# databank.net
KiCad netlist of a schematic drawn in EAGLE
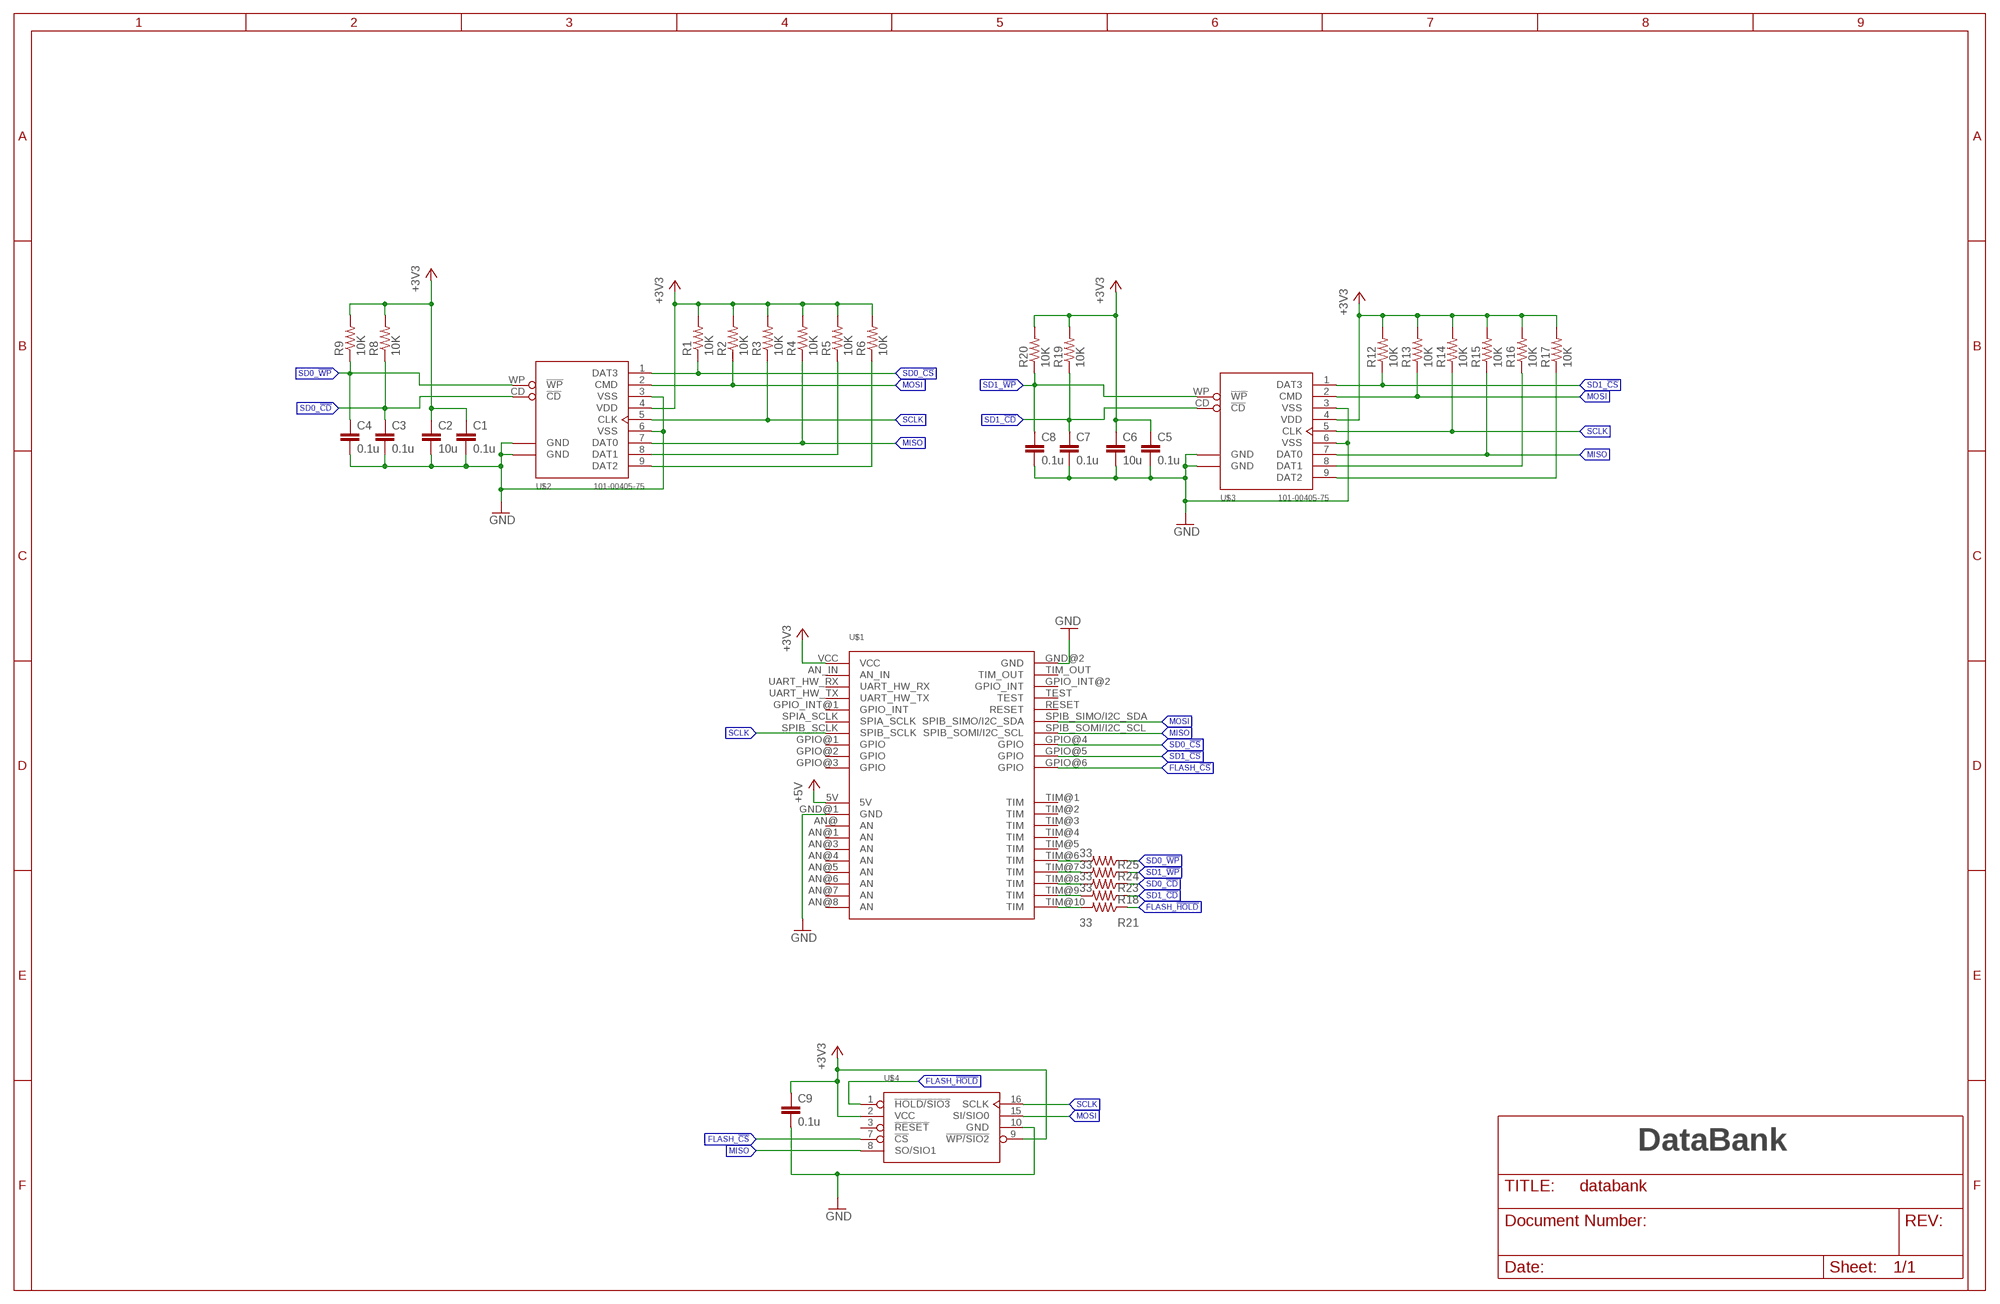
[diagram p0: schematic, sheet 1]

(export (version "E")
  (design (tool "Eeschema 10.0.6"))
  (components
    (comp (ref "C1")
      (value "0.1u")
      (footprint "eagle-import:C0603")
      (fields (field (name "MPN") "VJ0603V104ZXXCW1BC"))
      (libsource (lib "eagle-import") (part "C-EUC0603"))
    )
    (comp (ref "C2")
      (value "10u")
      (footprint "eagle-import:C0603")
      (fields (field (name "MPN") "LMK107BBJ106MALT"))
      (libsource (lib "eagle-import") (part "C-EUC0603"))
    )
    (comp (ref "C3")
      (value "0.1u")
      (footprint "eagle-import:C0603")
      (fields (field (name "MPN") "VJ0603V104ZXXCW1BC"))
      (libsource (lib "eagle-import") (part "C-EUC0603"))
    )
    (comp (ref "C4")
      (value "0.1u")
      (footprint "eagle-import:C0603")
      (fields (field (name "MPN") "VJ0603V104ZXXCW1BC"))
      (libsource (lib "eagle-import") (part "C-EUC0603"))
    )
    (comp (ref "C5")
      (value "0.1u")
      (footprint "eagle-import:C0603")
      (fields (field (name "MPN") "VJ0603V104ZXXCW1BC"))
      (libsource (lib "eagle-import") (part "C-EUC0603"))
    )
    (comp (ref "C6")
      (value "10u")
      (footprint "eagle-import:C0603")
      (fields (field (name "MPN") "LMK107BBJ106MALT"))
      (libsource (lib "eagle-import") (part "C-EUC0603"))
    )
    (comp (ref "C7")
      (value "0.1u")
      (footprint "eagle-import:C0603")
      (fields (field (name "MPN") "VJ0603V104ZXXCW1BC"))
      (libsource (lib "eagle-import") (part "C-EUC0603"))
    )
    (comp (ref "C8")
      (value "0.1u")
      (footprint "eagle-import:C0603")
      (fields (field (name "MPN") "VJ0603V104ZXXCW1BC"))
      (libsource (lib "eagle-import") (part "C-EUC0603"))
    )
    (comp (ref "C9")
      (value "0.1u")
      (footprint "eagle-import:C0603")
      (fields (field (name "MPN") "VJ0603V104ZXXCW1BC"))
      (libsource (lib "eagle-import") (part "C-EUC0603"))
    )
    (comp (ref "R1")
      (value "10K")
      (footprint "eagle-import:R0603")
      (fields (field (name "MPN") "WR06X1002FTL"))
      (libsource (lib "eagle-import") (part "R-US_R0603"))
    )
    (comp (ref "R2")
      (value "10K")
      (footprint "eagle-import:R0603")
      (fields (field (name "MPN") "WR06X1002FTL"))
      (libsource (lib "eagle-import") (part "R-US_R0603"))
    )
    (comp (ref "R3")
      (value "10K")
      (footprint "eagle-import:R0603")
      (fields (field (name "MPN") "WR06X1002FTL"))
      (libsource (lib "eagle-import") (part "R-US_R0603"))
    )
    (comp (ref "R4")
      (value "10K")
      (footprint "eagle-import:R0603")
      (fields (field (name "MPN") "WR06X1002FTL"))
      (libsource (lib "eagle-import") (part "R-US_R0603"))
    )
    (comp (ref "R5")
      (value "10K")
      (footprint "eagle-import:R0603")
      (fields (field (name "MPN") "WR06X1002FTL"))
      (libsource (lib "eagle-import") (part "R-US_R0603"))
    )
    (comp (ref "R6")
      (value "10K")
      (footprint "eagle-import:R0603")
      (fields (field (name "MPN") "WR06X1002FTL"))
      (libsource (lib "eagle-import") (part "R-US_R0603"))
    )
    (comp (ref "R8")
      (value "10K")
      (footprint "eagle-import:R0603")
      (fields (field (name "MPN") "WR06X1002FTL"))
      (libsource (lib "eagle-import") (part "R-US_R0603"))
    )
    (comp (ref "R9")
      (value "10K")
      (footprint "eagle-import:R0603")
      (fields (field (name "MPN") "WR06X1002FTL"))
      (libsource (lib "eagle-import") (part "R-US_R0603"))
    )
    (comp (ref "R12")
      (value "10K")
      (footprint "eagle-import:R0603")
      (fields (field (name "MPN") "WR06X1002FTL"))
      (libsource (lib "eagle-import") (part "R-US_R0603"))
    )
    (comp (ref "R13")
      (value "10K")
      (footprint "eagle-import:R0603")
      (fields (field (name "MPN") "WR06X1002FTL"))
      (libsource (lib "eagle-import") (part "R-US_R0603"))
    )
    (comp (ref "R14")
      (value "10K")
      (footprint "eagle-import:R0603")
      (fields (field (name "MPN") "WR06X1002FTL"))
      (libsource (lib "eagle-import") (part "R-US_R0603"))
    )
    (comp (ref "R15")
      (value "10K")
      (footprint "eagle-import:R0603")
      (fields (field (name "MPN") "WR06X1002FTL"))
      (libsource (lib "eagle-import") (part "R-US_R0603"))
    )
    (comp (ref "R16")
      (value "10K")
      (footprint "eagle-import:R0603")
      (fields (field (name "MPN") "WR06X1002FTL"))
      (libsource (lib "eagle-import") (part "R-US_R0603"))
    )
    (comp (ref "R17")
      (value "10K")
      (footprint "eagle-import:R0603")
      (fields (field (name "MPN") "WR06X1002FTL"))
      (libsource (lib "eagle-import") (part "R-US_R0603"))
    )
    (comp (ref "R18")
      (value "33")
      (footprint "eagle-import:R0603")
      (fields (field (name "MPN") "CR0402-JW-330GLF"))
      (libsource (lib "eagle-import") (part "R-US_R0603"))
    )
    (comp (ref "R19")
      (value "10K")
      (footprint "eagle-import:R0603")
      (fields (field (name "MPN") "WR06X1002FTL"))
      (libsource (lib "eagle-import") (part "R-US_R0603"))
    )
    (comp (ref "R20")
      (value "10K")
      (footprint "eagle-import:R0603")
      (fields (field (name "MPN") "WR06X1002FTL"))
      (libsource (lib "eagle-import") (part "R-US_R0603"))
    )
    (comp (ref "R21")
      (value "33")
      (footprint "eagle-import:R0603")
      (fields (field (name "MPN") "CR0402-JW-330GLF"))
      (libsource (lib "eagle-import") (part "R-US_R0603"))
    )
    (comp (ref "R23")
      (value "33")
      (footprint "eagle-import:R0603")
      (fields (field (name "MPN") "CR0402-JW-330GLF"))
      (libsource (lib "eagle-import") (part "R-US_R0603"))
    )
    (comp (ref "R24")
      (value "33")
      (footprint "eagle-import:R0603")
      (fields (field (name "MPN") "CR0402-JW-330GLF"))
      (libsource (lib "eagle-import") (part "R-US_R0603"))
    )
    (comp (ref "R25")
      (value "33")
      (footprint "eagle-import:R0603")
      (fields (field (name "MPN") "CR0402-JW-330GLF"))
      (libsource (lib "eagle-import") (part "R-US_R0603"))
    )
    (comp (ref "U$1")
      (value "LAUNCHPAD_BOOSTER_PACK")
      (footprint "eagle-import:LAUNCHPAD_BOOSTER_PACK")
      (libsource (lib "eagle-import") (part "LAUNCHPAD_BOOSTER_PACK"))
    )
    (comp (ref "U$2")
      (value "101-00405-75")
      (footprint "eagle-import:101-00405-75")
      (libsource (lib "eagle-import") (part "101-00405-75"))
    )
    (comp (ref "U$3")
      (value "101-00405-75")
      (footprint "eagle-import:101-00405-75")
      (libsource (lib "eagle-import") (part "101-00405-75"))
    )
    (comp (ref "U$4")
      (value "MX25L25635E")
      (footprint "eagle-import:SO-16LD")
      (libsource (lib "eagle-import") (part "MX25L25635E"))
    )
  )
  (nets
    (net (code "1") (name "+3V3") (class "Default")
      (node (ref "C1") (pin "1") (pinfunction "1_1") (pintype "passive"))
      (node (ref "C2") (pin "1") (pinfunction "1_1") (pintype "passive"))
      (node (ref "C5") (pin "1") (pinfunction "1_1") (pintype "passive"))
      (node (ref "C6") (pin "1") (pinfunction "1_1") (pintype "passive"))
      (node (ref "C9") (pin "1") (pinfunction "1_1") (pintype "passive"))
      (node (ref "R1") (pin "2") (pinfunction "2_2") (pintype "passive"))
      (node (ref "R12") (pin "2") (pinfunction "2_2") (pintype "passive"))
      (node (ref "R13") (pin "2") (pinfunction "2_2") (pintype "passive"))
      (node (ref "R14") (pin "2") (pinfunction "2_2") (pintype "passive"))
      (node (ref "R15") (pin "2") (pinfunction "2_2") (pintype "passive"))
      (node (ref "R16") (pin "2") (pinfunction "2_2") (pintype "passive"))
      (node (ref "R17") (pin "2") (pinfunction "2_2") (pintype "passive"))
      (node (ref "R19") (pin "2") (pinfunction "2_2") (pintype "passive"))
      (node (ref "R2") (pin "2") (pinfunction "2_2") (pintype "passive"))
      (node (ref "R20") (pin "2") (pinfunction "2_2") (pintype "passive"))
      (node (ref "R3") (pin "2") (pinfunction "2_2") (pintype "passive"))
      (node (ref "R4") (pin "2") (pinfunction "2_2") (pintype "passive"))
      (node (ref "R5") (pin "2") (pinfunction "2_2") (pintype "passive"))
      (node (ref "R6") (pin "2") (pinfunction "2_2") (pintype "passive"))
      (node (ref "R8") (pin "2") (pinfunction "2_2") (pintype "passive"))
      (node (ref "R9") (pin "2") (pinfunction "2_2") (pintype "passive"))
      (node (ref "U$1") (pin "VCC") (pinfunction "VCC_VCC") (pintype "power_in"))
      (node (ref "U$2") (pin "4") (pinfunction "VDD_4") (pintype "power_in"))
      (node (ref "U$3") (pin "4") (pinfunction "VDD_4") (pintype "power_in"))
      (node (ref "U$4") (pin "2") (pinfunction "VCC_2") (pintype "power_in"))
      (node (ref "U$4") (pin "9") (pinfunction "~{WP/SIO2}_9") (pintype "bidirectional"))
    )
    (net (code "2") (name "+5V") (class "Default")
      (node (ref "U$1") (pin "5V") (pinfunction "5V_5V") (pintype "power_in"))
    )
    (net (code "3") (name "/FLASH_~{CS}") (class "Default")
      (node (ref "U$1") (pin "GPIO@6") (pinfunction "GPIO_GPIO@6") (pintype "bidirectional"))
      (node (ref "U$4") (pin "7") (pinfunction "~{CS}_7") (pintype "input"))
    )
    (net (code "4") (name "/FLASH_~{HOLD}") (class "Default")
      (node (ref "R21") (pin "1") (pinfunction "1_1") (pintype "passive"))
      (node (ref "U$4") (pin "1") (pinfunction "~{HOLD/SIO3}_1") (pintype "bidirectional"))
    )
    (net (code "5") (name "/SD0_~{CD}") (class "Default")
      (node (ref "C3") (pin "1") (pinfunction "1_1") (pintype "passive"))
      (node (ref "R23") (pin "1") (pinfunction "1_1") (pintype "passive"))
      (node (ref "R8") (pin "1") (pinfunction "1_1") (pintype "passive"))
      (node (ref "U$2") (pin "CD") (pinfunction "~{CD}_CD") (pintype "passive"))
    )
    (net (code "6") (name "/SD0_~{CS}") (class "Default")
      (node (ref "R1") (pin "1") (pinfunction "1_1") (pintype "passive"))
      (node (ref "U$1") (pin "GPIO@4") (pinfunction "GPIO_GPIO@4") (pintype "bidirectional"))
      (node (ref "U$2") (pin "1") (pinfunction "DAT3_1") (pintype "bidirectional"))
    )
    (net (code "7") (name "/SD0_~{WP}") (class "Default")
      (node (ref "C4") (pin "1") (pinfunction "1_1") (pintype "passive"))
      (node (ref "R25") (pin "1") (pinfunction "1_1") (pintype "passive"))
      (node (ref "R9") (pin "1") (pinfunction "1_1") (pintype "passive"))
      (node (ref "U$2") (pin "WP") (pinfunction "~{WP}_WP") (pintype "passive"))
    )
    (net (code "8") (name "/SD1_~{CD}") (class "Default")
      (node (ref "C7") (pin "1") (pinfunction "1_1") (pintype "passive"))
      (node (ref "R18") (pin "1") (pinfunction "1_1") (pintype "passive"))
      (node (ref "R19") (pin "1") (pinfunction "1_1") (pintype "passive"))
      (node (ref "U$3") (pin "CD") (pinfunction "~{CD}_CD") (pintype "passive"))
    )
    (net (code "9") (name "/SD1_~{CS}") (class "Default")
      (node (ref "R12") (pin "1") (pinfunction "1_1") (pintype "passive"))
      (node (ref "U$1") (pin "GPIO@5") (pinfunction "GPIO_GPIO@5") (pintype "bidirectional"))
      (node (ref "U$3") (pin "1") (pinfunction "DAT3_1") (pintype "bidirectional"))
    )
    (net (code "10") (name "/SD1_~{WP}") (class "Default")
      (node (ref "C8") (pin "1") (pinfunction "1_1") (pintype "passive"))
      (node (ref "R20") (pin "1") (pinfunction "1_1") (pintype "passive"))
      (node (ref "R24") (pin "1") (pinfunction "1_1") (pintype "passive"))
      (node (ref "U$3") (pin "WP") (pinfunction "~{WP}_WP") (pintype "passive"))
    )
    (net (code "11") (name "GND") (class "Default")
      (node (ref "C1") (pin "2") (pinfunction "2_2") (pintype "passive"))
      (node (ref "C2") (pin "2") (pinfunction "2_2") (pintype "passive"))
      (node (ref "C3") (pin "2") (pinfunction "2_2") (pintype "passive"))
      (node (ref "C4") (pin "2") (pinfunction "2_2") (pintype "passive"))
      (node (ref "C5") (pin "2") (pinfunction "2_2") (pintype "passive"))
      (node (ref "C6") (pin "2") (pinfunction "2_2") (pintype "passive"))
      (node (ref "C7") (pin "2") (pinfunction "2_2") (pintype "passive"))
      (node (ref "C8") (pin "2") (pinfunction "2_2") (pintype "passive"))
      (node (ref "C9") (pin "2") (pinfunction "2_2") (pintype "passive"))
      (node (ref "U$1") (pin "GND@1") (pinfunction "GND_GND@1") (pintype "power_in"))
      (node (ref "U$1") (pin "GND@2") (pinfunction "GND_GND@2") (pintype "power_in"))
      (node (ref "U$2") (pin "3") (pinfunction "VSS_3") (pintype "power_in"))
      (node (ref "U$2") (pin "6") (pinfunction "VSS_6") (pintype "power_in"))
      (node (ref "U$2") (pin "G1$GND") (pinfunction "GND_G1$GND") (pintype "power_in"))
      (node (ref "U$2") (pin "G2$GND") (pinfunction "GND_G2$GND") (pintype "power_in"))
      (node (ref "U$3") (pin "3") (pinfunction "VSS_3") (pintype "power_in"))
      (node (ref "U$3") (pin "6") (pinfunction "VSS_6") (pintype "power_in"))
      (node (ref "U$3") (pin "G1$GND") (pinfunction "GND_G1$GND") (pintype "power_in"))
      (node (ref "U$3") (pin "G2$GND") (pinfunction "GND_G2$GND") (pintype "power_in"))
      (node (ref "U$4") (pin "10") (pinfunction "GND_10") (pintype "power_in"))
    )
    (net (code "12") (name "MISO") (class "Default")
      (node (ref "R15") (pin "1") (pinfunction "1_1") (pintype "passive"))
      (node (ref "R4") (pin "1") (pinfunction "1_1") (pintype "passive"))
      (node (ref "U$1") (pin "SPIB_SOMI/I2C_SCL") (pinfunction "SPIB_SOMI/I2C_SCL_SPIB_SOMI/I2C_SCL") (pintype "bidirectional"))
      (node (ref "U$2") (pin "7") (pinfunction "DAT0_7") (pintype "bidirectional"))
      (node (ref "U$3") (pin "7") (pinfunction "DAT0_7") (pintype "bidirectional"))
      (node (ref "U$4") (pin "8") (pinfunction "SO/SIO1_8") (pintype "bidirectional"))
    )
    (net (code "13") (name "MOSI") (class "Default")
      (node (ref "R13") (pin "1") (pinfunction "1_1") (pintype "passive"))
      (node (ref "R2") (pin "1") (pinfunction "1_1") (pintype "passive"))
      (node (ref "U$1") (pin "SPIB_SIMO/I2C_SDA") (pinfunction "SPIB_SIMO/I2C_SDA_SPIB_SIMO/I2C_SDA") (pintype "bidirectional"))
      (node (ref "U$2") (pin "2") (pinfunction "CMD_2") (pintype "bidirectional"))
      (node (ref "U$3") (pin "2") (pinfunction "CMD_2") (pintype "bidirectional"))
      (node (ref "U$4") (pin "15") (pinfunction "SI/SIO0_15") (pintype "bidirectional"))
    )
    (net (code "14") (name "Net-(R18-Pad2)") (class "Default")
      (node (ref "R18") (pin "2") (pinfunction "2_2") (pintype "passive"))
      (node (ref "U$1") (pin "TIM@9") (pinfunction "TIM_TIM@9") (pintype "bidirectional"))
    )
    (net (code "15") (name "Net-(R21-Pad2)") (class "Default")
      (node (ref "R21") (pin "2") (pinfunction "2_2") (pintype "passive"))
      (node (ref "U$1") (pin "TIM@10") (pinfunction "TIM_TIM@10") (pintype "bidirectional"))
    )
    (net (code "16") (name "Net-(R23-Pad2)") (class "Default")
      (node (ref "R23") (pin "2") (pinfunction "2_2") (pintype "passive"))
      (node (ref "U$1") (pin "TIM@8") (pinfunction "TIM_TIM@8") (pintype "bidirectional"))
    )
    (net (code "17") (name "Net-(R24-Pad2)") (class "Default")
      (node (ref "R24") (pin "2") (pinfunction "2_2") (pintype "passive"))
      (node (ref "U$1") (pin "TIM@7") (pinfunction "TIM_TIM@7") (pintype "bidirectional"))
    )
    (net (code "18") (name "Net-(R25-Pad2)") (class "Default")
      (node (ref "R25") (pin "2") (pinfunction "2_2") (pintype "passive"))
      (node (ref "U$1") (pin "TIM@6") (pinfunction "TIM_TIM@6") (pintype "bidirectional"))
    )
    (net (code "19") (name "Net-(U$2-DAT1)") (class "Default")
      (node (ref "R5") (pin "1") (pinfunction "1_1") (pintype "passive"))
      (node (ref "U$2") (pin "8") (pinfunction "DAT1_8") (pintype "bidirectional"))
    )
    (net (code "20") (name "Net-(U$2-DAT2)") (class "Default")
      (node (ref "R6") (pin "1") (pinfunction "1_1") (pintype "passive"))
      (node (ref "U$2") (pin "9") (pinfunction "DAT2_9") (pintype "bidirectional"))
    )
    (net (code "21") (name "Net-(U$3-DAT1)") (class "Default")
      (node (ref "R16") (pin "1") (pinfunction "1_1") (pintype "passive"))
      (node (ref "U$3") (pin "8") (pinfunction "DAT1_8") (pintype "bidirectional"))
    )
    (net (code "22") (name "Net-(U$3-DAT2)") (class "Default")
      (node (ref "R17") (pin "1") (pinfunction "1_1") (pintype "passive"))
      (node (ref "U$3") (pin "9") (pinfunction "DAT2_9") (pintype "bidirectional"))
    )
    (net (code "23") (name "SCLK") (class "Default")
      (node (ref "R14") (pin "1") (pinfunction "1_1") (pintype "passive"))
      (node (ref "R3") (pin "1") (pinfunction "1_1") (pintype "passive"))
      (node (ref "U$1") (pin "SPIB_SCLK") (pinfunction "SPIB_SCLK_SPIB_SCLK") (pintype "bidirectional"))
      (node (ref "U$2") (pin "5") (pinfunction "CLK_5") (pintype "input"))
      (node (ref "U$3") (pin "5") (pinfunction "CLK_5") (pintype "input"))
      (node (ref "U$4") (pin "16") (pinfunction "SCLK_16") (pintype "input"))
    )
    (net (code "24") (name "unconnected-(U$1-AN-PadAN@)") (class "Default")
      (node (ref "U$1") (pin "AN@") (pinfunction "AN_AN@") (pintype "bidirectional"))
    )
    (net (code "25") (name "unconnected-(U$1-AN-PadAN@1)") (class "Default")
      (node (ref "U$1") (pin "AN@1") (pinfunction "AN_AN@1") (pintype "bidirectional"))
    )
    (net (code "26") (name "unconnected-(U$1-AN-PadAN@3)") (class "Default")
      (node (ref "U$1") (pin "AN@3") (pinfunction "AN_AN@3") (pintype "bidirectional"))
    )
    (net (code "27") (name "unconnected-(U$1-AN-PadAN@4)") (class "Default")
      (node (ref "U$1") (pin "AN@4") (pinfunction "AN_AN@4") (pintype "bidirectional"))
    )
    (net (code "28") (name "unconnected-(U$1-AN-PadAN@5)") (class "Default")
      (node (ref "U$1") (pin "AN@5") (pinfunction "AN_AN@5") (pintype "bidirectional"))
    )
    (net (code "29") (name "unconnected-(U$1-AN-PadAN@6)") (class "Default")
      (node (ref "U$1") (pin "AN@6") (pinfunction "AN_AN@6") (pintype "bidirectional"))
    )
    (net (code "30") (name "unconnected-(U$1-AN-PadAN@7)") (class "Default")
      (node (ref "U$1") (pin "AN@7") (pinfunction "AN_AN@7") (pintype "bidirectional"))
    )
    (net (code "31") (name "unconnected-(U$1-AN-PadAN@8)") (class "Default")
      (node (ref "U$1") (pin "AN@8") (pinfunction "AN_AN@8") (pintype "bidirectional"))
    )
    (net (code "32") (name "unconnected-(U$1-GPIO-PadGPIO@1)") (class "Default")
      (node (ref "U$1") (pin "GPIO@1") (pinfunction "GPIO_GPIO@1") (pintype "bidirectional"))
    )
    (net (code "33") (name "unconnected-(U$1-GPIO-PadGPIO@2)") (class "Default")
      (node (ref "U$1") (pin "GPIO@2") (pinfunction "GPIO_GPIO@2") (pintype "bidirectional"))
    )
    (net (code "34") (name "unconnected-(U$1-GPIO-PadGPIO@3)") (class "Default")
      (node (ref "U$1") (pin "GPIO@3") (pinfunction "GPIO_GPIO@3") (pintype "bidirectional"))
    )
    (net (code "35") (name "unconnected-(U$1-GPIO_INT-PadGPIO_INT@1)") (class "Default")
      (node (ref "U$1") (pin "GPIO_INT@1") (pinfunction "GPIO_INT_GPIO_INT@1") (pintype "bidirectional"))
    )
    (net (code "36") (name "unconnected-(U$1-GPIO_INT-PadGPIO_INT@2)") (class "Default")
      (node (ref "U$1") (pin "GPIO_INT@2") (pinfunction "GPIO_INT_GPIO_INT@2") (pintype "bidirectional"))
    )
    (net (code "37") (name "unconnected-(U$1-PadAN_IN)") (class "Default")
      (node (ref "U$1") (pin "AN_IN") (pinfunction "AN_IN_AN_IN") (pintype "bidirectional"))
    )
    (net (code "38") (name "unconnected-(U$1-PadRESET)") (class "Default")
      (node (ref "U$1") (pin "RESET") (pinfunction "RESET_RESET") (pintype "bidirectional"))
    )
    (net (code "39") (name "unconnected-(U$1-PadSPIA_SCLK)") (class "Default")
      (node (ref "U$1") (pin "SPIA_SCLK") (pinfunction "SPIA_SCLK_SPIA_SCLK") (pintype "bidirectional"))
    )
    (net (code "40") (name "unconnected-(U$1-PadTEST)") (class "Default")
      (node (ref "U$1") (pin "TEST") (pinfunction "TEST_TEST") (pintype "bidirectional"))
    )
    (net (code "41") (name "unconnected-(U$1-PadTIM_OUT)") (class "Default")
      (node (ref "U$1") (pin "TIM_OUT") (pinfunction "TIM_OUT_TIM_OUT") (pintype "bidirectional"))
    )
    (net (code "42") (name "unconnected-(U$1-PadUART_HW_RX)") (class "Default")
      (node (ref "U$1") (pin "UART_HW_RX") (pinfunction "UART_HW_RX_UART_HW_RX") (pintype "bidirectional"))
    )
    (net (code "43") (name "unconnected-(U$1-PadUART_HW_TX)") (class "Default")
      (node (ref "U$1") (pin "UART_HW_TX") (pinfunction "UART_HW_TX_UART_HW_TX") (pintype "bidirectional"))
    )
    (net (code "44") (name "unconnected-(U$1-TIM-PadTIM@1)") (class "Default")
      (node (ref "U$1") (pin "TIM@1") (pinfunction "TIM_TIM@1") (pintype "bidirectional"))
    )
    (net (code "45") (name "unconnected-(U$1-TIM-PadTIM@2)") (class "Default")
      (node (ref "U$1") (pin "TIM@2") (pinfunction "TIM_TIM@2") (pintype "bidirectional"))
    )
    (net (code "46") (name "unconnected-(U$1-TIM-PadTIM@3)") (class "Default")
      (node (ref "U$1") (pin "TIM@3") (pinfunction "TIM_TIM@3") (pintype "bidirectional"))
    )
    (net (code "47") (name "unconnected-(U$1-TIM-PadTIM@4)") (class "Default")
      (node (ref "U$1") (pin "TIM@4") (pinfunction "TIM_TIM@4") (pintype "bidirectional"))
    )
    (net (code "48") (name "unconnected-(U$1-TIM-PadTIM@5)") (class "Default")
      (node (ref "U$1") (pin "TIM@5") (pinfunction "TIM_TIM@5") (pintype "bidirectional"))
    )
    (net (code "49") (name "unconnected-(U$4-~{RESET}-Pad3)") (class "Default")
      (node (ref "U$4") (pin "3") (pinfunction "~{RESET}_3") (pintype "input"))
    )
  )
)
